# Schematic_v21.net
KiCad netlist of a schematic drawn in EAGLE
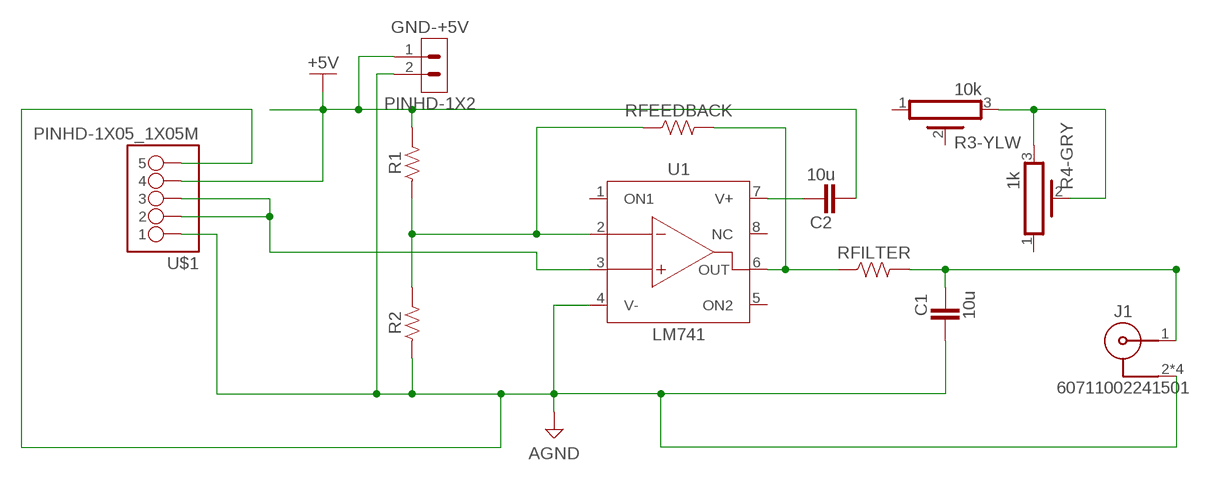
[diagram p0: schematic, sheet 1]

(export (version "E")
  (design (tool "Eeschema 10.0.6"))
  (components
    (comp (ref "C1")
      (value "10u")
      (footprint "eagle-import:CAP-THRU-2.54MM")
      (libsource (lib "eagle-import") (part "CAPACITORCERAMIC-2.54MM"))
    )
    (comp (ref "C2")
      (value "10u")
      (footprint "eagle-import:CAP-THRU-2.54MM")
      (libsource (lib "eagle-import") (part "CAPACITORCERAMIC-2.54MM"))
    )
    (comp (ref "GND-+5V")
      (value "PINHD-1X2")
      (footprint "eagle-import:1X02")
      (libsource (lib "eagle-import") (part "PINHD-1X2"))
    )
    (comp (ref "J1")
      (value "60711002241501")
      (footprint "eagle-import:60711002241501")
      (libsource (lib "eagle-import") (part "60711002241501"))
    )
    (comp (ref "R1")
      (value "1k")
      (footprint "eagle-import:RESAD724W46L381D178B")
      (libsource (lib "eagle-import") (part "R-USAXIAL-7.2MM-PITCH_"))
    )
    (comp (ref "R2")
      (value "1k")
      (footprint "eagle-import:RESAD724W46L381D178B")
      (libsource (lib "eagle-import") (part "R-USAXIAL-7.2MM-PITCH_"))
    )
    (comp (ref "R3-YLW")
      (value "10k")
      (footprint "eagle-import:HA-06-SM065")
      (libsource (lib "eagle-import") (part "POT_HA-06"))
    )
    (comp (ref "R4-GRY")
      (value "1k")
      (footprint "eagle-import:HA-06-SM065")
      (libsource (lib "eagle-import") (part "POT_HA-06"))
    )
    (comp (ref "RFEEDBACK")
      (value "24M")
      (footprint "eagle-import:RESAD724W46L381D178B")
      (libsource (lib "eagle-import") (part "R-USAXIAL-7.2MM-PITCH_"))
    )
    (comp (ref "RFILTER")
      (value "47k")
      (footprint "eagle-import:RESAD724W46L381D178B")
      (libsource (lib "eagle-import") (part "R-USAXIAL-7.2MM-PITCH_"))
    )
    (comp (ref "U$1")
      (value "PINHD-1X05_1X05M")
      (footprint "eagle-import:1X05")
      (libsource (lib "eagle-import") (part "PINHD-1X05_1X05M"))
    )
    (comp (ref "U1")
      (value "LM741")
      (footprint "eagle-import:DIP826W53P254L959H508Q8B")
      (libsource (lib "eagle-import") (part "LM741"))
    )
  )
  (nets
    (net (code "1") (name "+5V") (class "Default")
      (node (ref "C2") (pin "2") (pinfunction "2_2") (pintype "passive"))
      (node (ref "GND-+5V") (pin "1") (pinfunction "1_1") (pintype "passive"))
      (node (ref "R1") (pin "2") (pinfunction "2_2") (pintype "passive"))
      (node (ref "U$1") (pin "4") (pinfunction "4_4") (pintype "bidirectional"))
    )
    (net (code "2") (name "AGND") (class "Default")
      (node (ref "C1") (pin "2") (pinfunction "2_2") (pintype "passive"))
      (node (ref "GND-+5V") (pin "2") (pinfunction "2_2") (pintype "passive"))
      (node (ref "J1") (pin "2") (pinfunction "2_2") (pintype "passive"))
      (node (ref "J1") (pin "3") (pinfunction "2_3") (pintype "passive"))
      (node (ref "J1") (pin "4") (pinfunction "2_4") (pintype "passive"))
      (node (ref "J1") (pin "5") (pinfunction "2_5") (pintype "passive"))
      (node (ref "R2") (pin "1") (pinfunction "1_1") (pintype "passive"))
      (node (ref "U$1") (pin "1") (pinfunction "1_1") (pintype "bidirectional"))
      (node (ref "U$1") (pin "5") (pinfunction "5_5") (pintype "bidirectional"))
      (node (ref "U1") (pin "4") (pinfunction "V-_4") (pintype "bidirectional"))
    )
    (net (code "3") (name "Net-(C1-Pad1)") (class "Default")
      (node (ref "C1") (pin "1") (pinfunction "1_1") (pintype "passive"))
      (node (ref "J1") (pin "1") (pinfunction "1_1") (pintype "passive"))
      (node (ref "RFILTER") (pin "2") (pinfunction "2_2") (pintype "passive"))
    )
    (net (code "4") (name "Net-(R3-YLW-P$3)") (class "Default")
      (node (ref "R3-YLW") (pin "3") (pinfunction "P$3_3") (pintype "passive"))
      (node (ref "R4-GRY") (pin "2") (pinfunction "P$2_2") (pintype "passive"))
      (node (ref "R4-GRY") (pin "3") (pinfunction "P$3_3") (pintype "passive"))
    )
    (net (code "5") (name "Net-(U1-+IN)") (class "Default")
      (node (ref "U$1") (pin "2") (pinfunction "2_2") (pintype "bidirectional"))
      (node (ref "U$1") (pin "3") (pinfunction "3_3") (pintype "bidirectional"))
      (node (ref "U1") (pin "3") (pinfunction "+IN_3") (pintype "input"))
    )
    (net (code "6") (name "Net-(U1--IN)") (class "Default")
      (node (ref "R1") (pin "1") (pinfunction "1_1") (pintype "passive"))
      (node (ref "R2") (pin "2") (pinfunction "2_2") (pintype "passive"))
      (node (ref "RFEEDBACK") (pin "1") (pinfunction "1_1") (pintype "passive"))
      (node (ref "U1") (pin "2") (pinfunction "-IN_2") (pintype "input"))
    )
    (net (code "7") (name "Net-(U1-OUT)") (class "Default")
      (node (ref "RFEEDBACK") (pin "2") (pinfunction "2_2") (pintype "passive"))
      (node (ref "RFILTER") (pin "1") (pinfunction "1_1") (pintype "passive"))
      (node (ref "U1") (pin "6") (pinfunction "OUT_6") (pintype "output"))
    )
    (net (code "8") (name "Net-(U1-V+)") (class "Default")
      (node (ref "C2") (pin "1") (pinfunction "1_1") (pintype "passive"))
      (node (ref "U1") (pin "7") (pinfunction "V+_7") (pintype "bidirectional"))
    )
    (net (code "9") (name "unconnected-(R3-YLW-P$1-Pad1)") (class "Default")
      (node (ref "R3-YLW") (pin "1") (pinfunction "P$1_1") (pintype "passive"))
    )
    (net (code "10") (name "unconnected-(R3-YLW-P$2-Pad2)") (class "Default")
      (node (ref "R3-YLW") (pin "2") (pinfunction "P$2_2") (pintype "passive"))
    )
    (net (code "11") (name "unconnected-(R4-GRY-P$1-Pad1)") (class "Default")
      (node (ref "R4-GRY") (pin "1") (pinfunction "P$1_1") (pintype "passive"))
    )
    (net (code "12") (name "unconnected-(U1-NC-Pad8)") (class "Default")
      (node (ref "U1") (pin "8") (pinfunction "NC_8") (pintype "passive"))
    )
    (net (code "13") (name "unconnected-(U1-ON1-Pad1)") (class "Default")
      (node (ref "U1") (pin "1") (pinfunction "ON1_1") (pintype "passive"))
    )
    (net (code "14") (name "unconnected-(U1-ON2-Pad5)") (class "Default")
      (node (ref "U1") (pin "5") (pinfunction "ON2_5") (pintype "passive"))
    )
  )
)
